# G07___PCB__2024-07-05.net
KiCad netlist of a schematic drawn in EasyEDA Pro
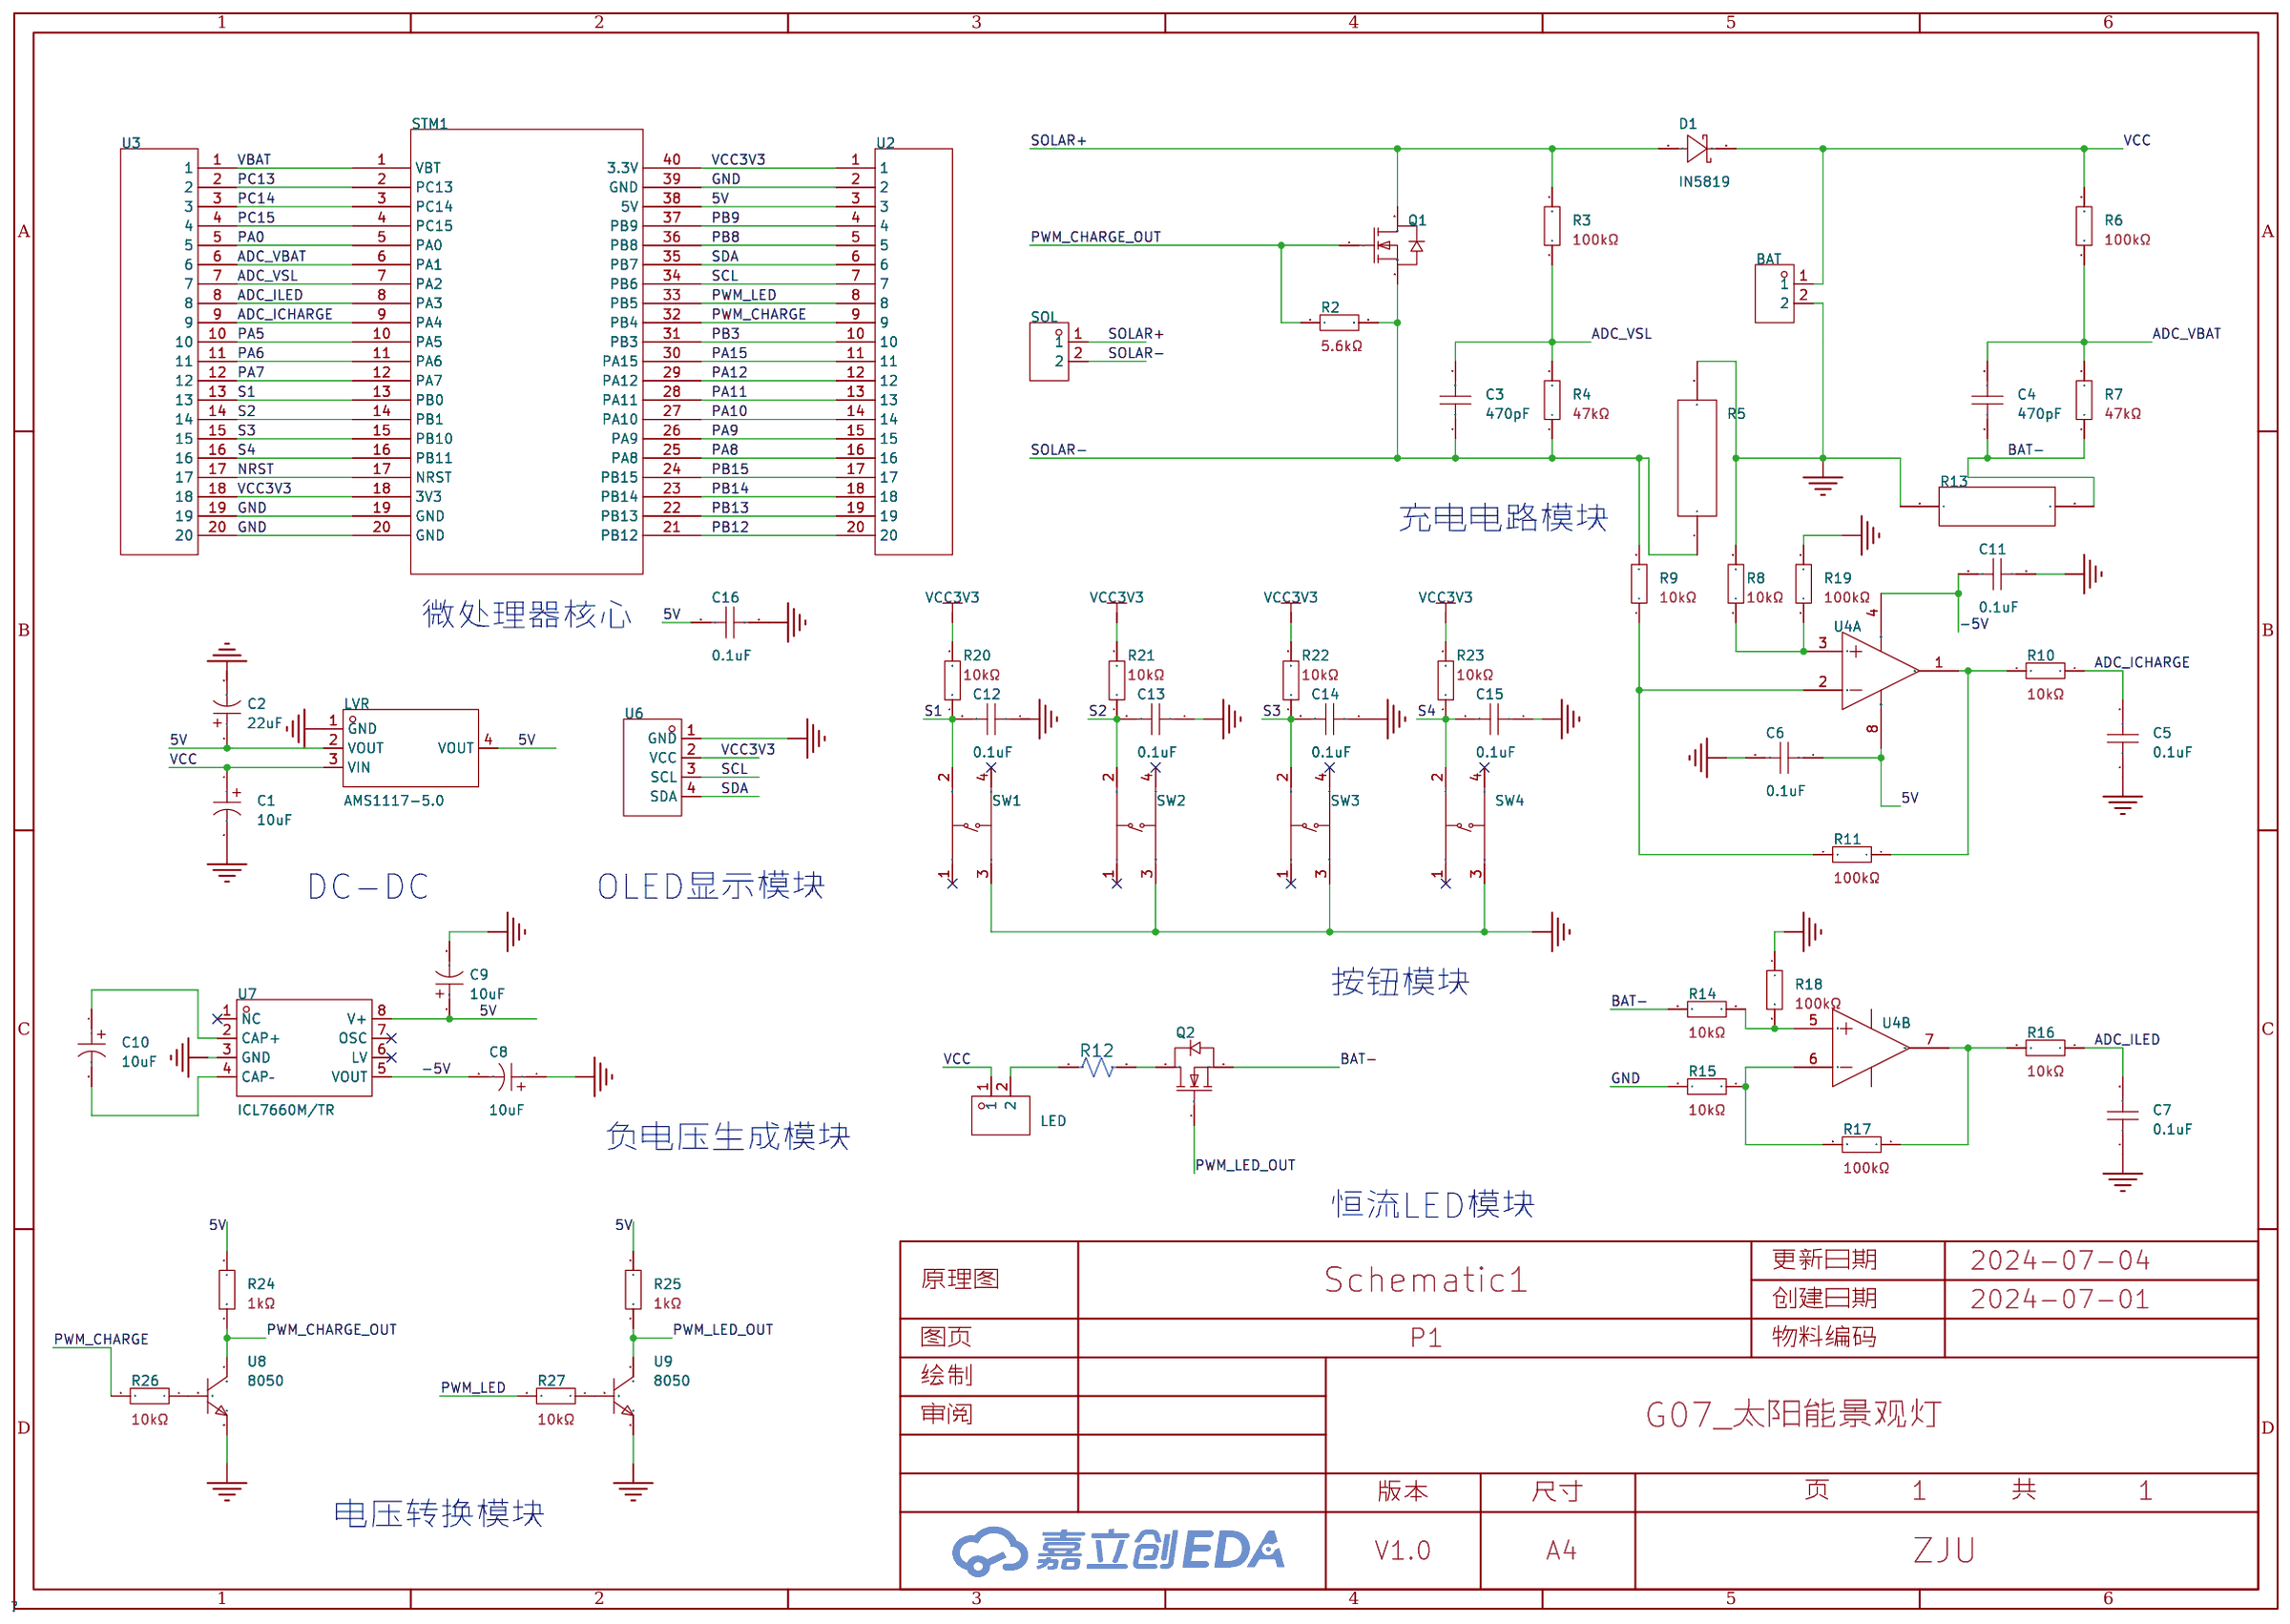
[diagram p0: schematic sheet]

(export (version "E")
  (design (tool "Eeschema 10.0.6"))
  (components
    (comp (ref "BAT")
      (value "KF2EDGK-5.08-2P")
      (footprint "easyedapro:CONN-TH_2P-P5.08_DB2EVC-5.08-2P-BK")
      (libsource (lib "easyedapro") (part "KF2EDGK-5.08-2P"))
    )
    (comp (ref "C1")
      (value "10uF")
      (footprint "easyedapro:C0511_直插电解")
      (description "C0511直插电解电容")
      (libsource (lib "easyedapro") (part "C0511"))
    )
    (comp (ref "C2")
      (value "22uF")
      (footprint "easyedapro:C0511_直插电解")
      (description "C0511直插电解电容")
      (libsource (lib "easyedapro") (part "C0511"))
    )
    (comp (ref "C3")
      (value "470pF")
      (footprint "easyedapro:CAP-TH_L5.3-W3.2-P2.54-D0.6-S2.65")
      (description "容值:100nF;精度:-20%~+80%;额定电压:50V;温度系数:Y5V;")
      (fields
        (field (name "Manufacturer Part") "CC1H104ZA1ED3F5O1100")
        (field (name "Manufacturer") "Dersonic(德尔创)")
      )
      (libsource (lib "easyedapro") (part "CC1H104ZA1ED3F5O1100"))
    )
    (comp (ref "C4")
      (value "470pF")
      (footprint "easyedapro:CAP-TH_L5.3-W3.2-P2.54-D0.6-S2.65")
      (description "容值:100nF;精度:-20%~+80%;额定电压:50V;温度系数:Y5V;")
      (fields
        (field (name "Manufacturer Part") "CC1H104ZA1ED3F5O1100")
        (field (name "Manufacturer") "Dersonic(德尔创)")
      )
      (libsource (lib "easyedapro") (part "CC1H104ZA1ED3F5O1100"))
    )
    (comp (ref "C5")
      (value "0.1uF")
      (footprint "easyedapro:CAP-TH_L5.3-W3.2-P2.54-D0.6-S2.65")
      (description "容值:100nF;精度:-20%~+80%;额定电压:50V;温度系数:Y5V;")
      (fields
        (field (name "Manufacturer Part") "CC1H104ZA1ED3F5O1100")
        (field (name "Manufacturer") "Dersonic(德尔创)")
      )
      (libsource (lib "easyedapro") (part "CC1H104ZA1ED3F5O1100"))
    )
    (comp (ref "C6")
      (value "0.1uF")
      (footprint "easyedapro:CAP-TH_L5.3-W3.2-P2.54-D0.6-S2.65")
      (description "容值:100nF;精度:-20%~+80%;额定电压:50V;温度系数:Y5V;")
      (fields
        (field (name "Manufacturer Part") "CC1H104ZA1ED3F5O1100")
        (field (name "Manufacturer") "Dersonic(德尔创)")
      )
      (libsource (lib "easyedapro") (part "CC1H104ZA1ED3F5O1100"))
    )
    (comp (ref "C7")
      (value "0.1uF")
      (footprint "easyedapro:CAP-TH_L5.3-W3.2-P2.54-D0.6-S2.65")
      (description "容值:100nF;精度:-20%~+80%;额定电压:50V;温度系数:Y5V;")
      (fields
        (field (name "Manufacturer Part") "CC1H104ZA1ED3F5O1100")
        (field (name "Manufacturer") "Dersonic(德尔创)")
      )
      (libsource (lib "easyedapro") (part "CC1H104ZA1ED3F5O1100"))
    )
    (comp (ref "C8")
      (value "10uF")
      (footprint "easyedapro:C0511_直插电解")
      (description "C0511直插电解电容")
      (libsource (lib "easyedapro") (part "C0511"))
    )
    (comp (ref "C9")
      (value "10uF")
      (footprint "easyedapro:C0511_直插电解")
      (description "C0511直插电解电容")
      (libsource (lib "easyedapro") (part "C0511"))
    )
    (comp (ref "C10")
      (value "10uF")
      (footprint "easyedapro:C0511_直插电解")
      (description "C0511直插电解电容")
      (libsource (lib "easyedapro") (part "C0511"))
    )
    (comp (ref "C11")
      (value "0.1uF")
      (footprint "easyedapro:CAP-TH_L5.3-W3.2-P2.54-D0.6-S2.65")
      (description "容值:100nF;精度:-20%~+80%;额定电压:50V;温度系数:Y5V;")
      (fields
        (field (name "Manufacturer Part") "CC1H104ZA1ED3F5O1100")
        (field (name "Manufacturer") "Dersonic(德尔创)")
      )
      (libsource (lib "easyedapro") (part "CC1H104ZA1ED3F5O1100"))
    )
    (comp (ref "C12")
      (value "0.1uF")
      (footprint "easyedapro:CAP-TH_L5.3-W3.2-P2.54-D0.6-S2.65")
      (description "容值:100nF;精度:-20%~+80%;额定电压:50V;温度系数:Y5V;")
      (fields
        (field (name "Manufacturer Part") "CC1H104ZA1ED3F5O1100")
        (field (name "Manufacturer") "Dersonic(德尔创)")
      )
      (libsource (lib "easyedapro") (part "CC1H104ZA1ED3F5O1100"))
    )
    (comp (ref "C13")
      (value "0.1uF")
      (footprint "easyedapro:CAP-TH_L5.3-W3.2-P2.54-D0.6-S2.65")
      (description "容值:100nF;精度:-20%~+80%;额定电压:50V;温度系数:Y5V;")
      (fields
        (field (name "Manufacturer Part") "CC1H104ZA1ED3F5O1100")
        (field (name "Manufacturer") "Dersonic(德尔创)")
      )
      (libsource (lib "easyedapro") (part "CC1H104ZA1ED3F5O1100"))
    )
    (comp (ref "C14")
      (value "0.1uF")
      (footprint "easyedapro:CAP-TH_L5.3-W3.2-P2.54-D0.6-S2.65")
      (description "容值:100nF;精度:-20%~+80%;额定电压:50V;温度系数:Y5V;")
      (fields
        (field (name "Manufacturer Part") "CC1H104ZA1ED3F5O1100")
        (field (name "Manufacturer") "Dersonic(德尔创)")
      )
      (libsource (lib "easyedapro") (part "CC1H104ZA1ED3F5O1100"))
    )
    (comp (ref "C15")
      (value "0.1uF")
      (footprint "easyedapro:CAP-TH_L5.3-W3.2-P2.54-D0.6-S2.65")
      (description "容值:100nF;精度:-20%~+80%;额定电压:50V;温度系数:Y5V;")
      (fields
        (field (name "Manufacturer Part") "CC1H104ZA1ED3F5O1100")
        (field (name "Manufacturer") "Dersonic(德尔创)")
      )
      (libsource (lib "easyedapro") (part "CC1H104ZA1ED3F5O1100"))
    )
    (comp (ref "C16")
      (value "0.1uF")
      (footprint "easyedapro:CAP-TH_L5.3-W3.2-P2.54-D0.6-S2.65")
      (description "容值:100nF;精度:-20%~+80%;额定电压:50V;温度系数:Y5V;")
      (fields
        (field (name "Manufacturer Part") "CC1H104ZA1ED3F5O1100")
        (field (name "Manufacturer") "Dersonic(德尔创)")
      )
      (libsource (lib "easyedapro") (part "CC1H104ZA1ED3F5O1100"))
    )
    (comp (ref "D1")
      (value "IN5819")
      (footprint "easyedapro:DO-41_BD2.4-L4.7-P8.70-D0.8-FD")
      (libsource (lib "easyedapro") (part "IN5819"))
    )
    (comp (ref "LED")
      (value "KF2EDGK-5.08-2P")
      (footprint "easyedapro:CONN-TH_2P-P5.08_DB2EVC-5.08-2P-BK")
      (libsource (lib "easyedapro") (part "KF2EDGK-5.08-2P"))
    )
    (comp (ref "LVR")
      (value "AMS1117-5.0")
      (footprint "easyedapro:SOT-223_L6.5-W3.5-P2.30-LS7.0-BR")
      (description "输出类型:固定;最大输入电压:12V;输出电压:5V;最大输出电流:1A;电源纹波抑制比(PSRR):68dB@(120Hz);输出极性:正极;")
      (fields (field (name "Manufacturer") "AMS"))
      (libsource (lib "easyedapro") (part "AMS1117-5.0"))
    )
    (comp (ref "Q1")
      (value "STP75NF75")
      (footprint "easyedapro:TO-220-3_L10.0-W4.5-P2.54-L")
      (fields (field (name "Manufacturer") "ST(意法半导体)"))
      (libsource (lib "easyedapro") (part "STP75NF75"))
    )
    (comp (ref "Q2")
      (value "STP75NF75")
      (footprint "easyedapro:TO-220-3_L10.0-W4.5-P2.54-L")
      (fields (field (name "Manufacturer") "ST(意法半导体)"))
      (libsource (lib "easyedapro") (part "STP75NF75"))
    )
    (comp (ref "R2")
      (value "AXIAL-0.4")
      (footprint "easyedapro:RES-TH_BD2.7-L8.8-P12.80-D0.5")
      (fields (field (name "Resistance") "5.6kΩ"))
      (libsource (lib "easyedapro") (part "AXIAL-0.4_C9900024059"))
    )
    (comp (ref "R3")
      (value "AXIAL-0.4")
      (footprint "easyedapro:RES-TH_BD2.7-L8.8-P12.80-D0.5")
      (fields (field (name "Resistance") "100kΩ"))
      (libsource (lib "easyedapro") (part "AXIAL-0.4_C9900024059"))
    )
    (comp (ref "R4")
      (value "AXIAL-0.4")
      (footprint "easyedapro:RES-TH_BD2.7-L8.8-P12.80-D0.5")
      (fields (field (name "Resistance") "47kΩ"))
      (libsource (lib "easyedapro") (part "AXIAL-0.4_C9900024059"))
    )
    (comp (ref "R5")
      (value "~")
      (footprint "easyedapro:采样电阻2*10mm")
      (libsource (lib "easyedapro") (part "采样电阻"))
    )
    (comp (ref "R6")
      (value "AXIAL-0.4")
      (footprint "easyedapro:RES-TH_BD2.7-L8.8-P12.80-D0.5")
      (fields (field (name "Resistance") "100kΩ"))
      (libsource (lib "easyedapro") (part "AXIAL-0.4_C9900024059"))
    )
    (comp (ref "R7")
      (value "AXIAL-0.4")
      (footprint "easyedapro:RES-TH_BD2.7-L8.8-P12.80-D0.5")
      (fields (field (name "Resistance") "47kΩ"))
      (libsource (lib "easyedapro") (part "AXIAL-0.4_C9900024059"))
    )
    (comp (ref "R8")
      (value "AXIAL-0.4")
      (footprint "easyedapro:RES-TH_BD2.7-L8.8-P12.80-D0.5")
      (fields (field (name "Resistance") "10kΩ"))
      (libsource (lib "easyedapro") (part "AXIAL-0.4_C9900024059"))
    )
    (comp (ref "R9")
      (value "AXIAL-0.4")
      (footprint "easyedapro:RES-TH_BD2.7-L8.8-P12.80-D0.5")
      (fields (field (name "Resistance") "10kΩ"))
      (libsource (lib "easyedapro") (part "AXIAL-0.4_C9900024059"))
    )
    (comp (ref "R10")
      (value "AXIAL-0.4")
      (footprint "easyedapro:RES-TH_BD2.7-L8.8-P12.80-D0.5")
      (fields (field (name "Resistance") "10kΩ"))
      (libsource (lib "easyedapro") (part "AXIAL-0.4_C9900024059"))
    )
    (comp (ref "R11")
      (value "AXIAL-0.4")
      (footprint "easyedapro:RES-TH_BD2.7-L8.8-P12.80-D0.5")
      (fields (field (name "Resistance") "100kΩ"))
      (libsource (lib "easyedapro") (part "AXIAL-0.4_C9900024059"))
    )
    (comp (ref "R12")
      (value "~")
      (footprint "easyedapro:AXIAL_0.6")
      (libsource (lib "easyedapro") (part "Resistor"))
    )
    (comp (ref "R13")
      (value "~")
      (footprint "easyedapro:采样电阻2*10mm")
      (libsource (lib "easyedapro") (part "采样电阻"))
    )
    (comp (ref "R14")
      (value "AXIAL-0.4")
      (footprint "easyedapro:RES-TH_BD2.7-L8.8-P12.80-D0.5")
      (fields (field (name "Resistance") "10kΩ"))
      (libsource (lib "easyedapro") (part "AXIAL-0.4_C9900024059"))
    )
    (comp (ref "R15")
      (value "AXIAL-0.4")
      (footprint "easyedapro:RES-TH_BD2.7-L8.8-P12.80-D0.5")
      (fields (field (name "Resistance") "10kΩ"))
      (libsource (lib "easyedapro") (part "AXIAL-0.4_C9900024059"))
    )
    (comp (ref "R16")
      (value "AXIAL-0.4")
      (footprint "easyedapro:RES-TH_BD2.7-L8.8-P12.80-D0.5")
      (fields (field (name "Resistance") "10kΩ"))
      (libsource (lib "easyedapro") (part "AXIAL-0.4_C9900024059"))
    )
    (comp (ref "R17")
      (value "AXIAL-0.4")
      (footprint "easyedapro:RES-TH_BD2.7-L8.8-P12.80-D0.5")
      (fields (field (name "Resistance") "100kΩ"))
      (libsource (lib "easyedapro") (part "AXIAL-0.4_C9900024059"))
    )
    (comp (ref "R18")
      (value "AXIAL-0.4")
      (footprint "easyedapro:RES-TH_BD2.7-L8.8-P12.80-D0.5")
      (fields (field (name "Resistance") "100kΩ"))
      (libsource (lib "easyedapro") (part "AXIAL-0.4_C9900024059"))
    )
    (comp (ref "R19")
      (value "AXIAL-0.4")
      (footprint "easyedapro:RES-TH_BD2.7-L8.8-P12.80-D0.5")
      (fields (field (name "Resistance") "100kΩ"))
      (libsource (lib "easyedapro") (part "AXIAL-0.4_C9900024059"))
    )
    (comp (ref "R20")
      (value "AXIAL-0.4")
      (footprint "easyedapro:RES-TH_BD2.7-L8.8-P12.80-D0.5")
      (fields (field (name "Resistance") "10kΩ"))
      (libsource (lib "easyedapro") (part "AXIAL-0.4_C9900024059"))
    )
    (comp (ref "R21")
      (value "AXIAL-0.4")
      (footprint "easyedapro:RES-TH_BD2.7-L8.8-P12.80-D0.5")
      (fields (field (name "Resistance") "10kΩ"))
      (libsource (lib "easyedapro") (part "AXIAL-0.4_C9900024059"))
    )
    (comp (ref "R22")
      (value "AXIAL-0.4")
      (footprint "easyedapro:RES-TH_BD2.7-L8.8-P12.80-D0.5")
      (fields (field (name "Resistance") "10kΩ"))
      (libsource (lib "easyedapro") (part "AXIAL-0.4_C9900024059"))
    )
    (comp (ref "R23")
      (value "AXIAL-0.4")
      (footprint "easyedapro:RES-TH_BD2.7-L8.8-P12.80-D0.5")
      (fields (field (name "Resistance") "10kΩ"))
      (libsource (lib "easyedapro") (part "AXIAL-0.4_C9900024059"))
    )
    (comp (ref "R24")
      (value "AXIAL-0.4")
      (footprint "easyedapro:RES-TH_BD2.7-L8.8-P12.80-D0.5")
      (fields (field (name "Resistance") "1kΩ"))
      (libsource (lib "easyedapro") (part "AXIAL-0.4_C9900024059"))
    )
    (comp (ref "R25")
      (value "AXIAL-0.4")
      (footprint "easyedapro:RES-TH_BD2.7-L8.8-P12.80-D0.5")
      (fields (field (name "Resistance") "1kΩ"))
      (libsource (lib "easyedapro") (part "AXIAL-0.4_C9900024059"))
    )
    (comp (ref "R26")
      (value "AXIAL-0.4")
      (footprint "easyedapro:RES-TH_BD2.7-L8.8-P12.80-D0.5")
      (fields (field (name "Resistance") "10kΩ"))
      (libsource (lib "easyedapro") (part "AXIAL-0.4_C9900024059"))
    )
    (comp (ref "R27")
      (value "AXIAL-0.4")
      (footprint "easyedapro:RES-TH_BD2.7-L8.8-P12.80-D0.5")
      (fields (field (name "Resistance") "10kΩ"))
      (libsource (lib "easyedapro") (part "AXIAL-0.4_C9900024059"))
    )
    (comp (ref "SOL")
      (value "KF2EDGK-5.08-2P")
      (footprint "easyedapro:CONN-TH_2P-P5.08_DB2EVC-5.08-2P-BK")
      (libsource (lib "easyedapro") (part "KF2EDGK-5.08-2P"))
    )
    (comp (ref "STM1")
      (value "STM32103C8T6")
      (footprint "easyedapro:STM32_C8T6_核心板")
      (libsource (lib "easyedapro") (part "STM32103C8T6_核心板"))
    )
    (comp (ref "SW1")
      (value "TS665CJ")
      (footprint "easyedapro:SW-TH_4P-L6.0-W6.0-P4.50-LS6.5")
      (description "电路结构:单刀单掷;按钮形状:圆形按钮;安装方式:直插;开关长度:6mm;开关宽度:6mm;开关高度:5mm;触点电流:50mA;额定电压(DC):12V;带灯:-;机械寿命:-;")
      (fields (field (name "Manufacturer") "SHOU HAN(首韩)"))
      (libsource (lib "easyedapro") (part "TS665CJ"))
    )
    (comp (ref "SW2")
      (value "TS665CJ")
      (footprint "easyedapro:SW-TH_4P-L6.0-W6.0-P4.50-LS6.5")
      (description "电路结构:单刀单掷;按钮形状:圆形按钮;安装方式:直插;开关长度:6mm;开关宽度:6mm;开关高度:5mm;触点电流:50mA;额定电压(DC):12V;带灯:-;机械寿命:-;")
      (fields (field (name "Manufacturer") "SHOU HAN(首韩)"))
      (libsource (lib "easyedapro") (part "TS665CJ"))
    )
    (comp (ref "SW3")
      (value "TS665CJ")
      (footprint "easyedapro:SW-TH_4P-L6.0-W6.0-P4.50-LS6.5")
      (description "电路结构:单刀单掷;按钮形状:圆形按钮;安装方式:直插;开关长度:6mm;开关宽度:6mm;开关高度:5mm;触点电流:50mA;额定电压(DC):12V;带灯:-;机械寿命:-;")
      (fields (field (name "Manufacturer") "SHOU HAN(首韩)"))
      (libsource (lib "easyedapro") (part "TS665CJ"))
    )
    (comp (ref "SW4")
      (value "TS665CJ")
      (footprint "easyedapro:SW-TH_4P-L6.0-W6.0-P4.50-LS6.5")
      (description "电路结构:单刀单掷;按钮形状:圆形按钮;安装方式:直插;开关长度:6mm;开关宽度:6mm;开关高度:5mm;触点电流:50mA;额定电压(DC):12V;带灯:-;机械寿命:-;")
      (fields (field (name "Manufacturer") "SHOU HAN(首韩)"))
      (libsource (lib "easyedapro") (part "TS665CJ"))
    )
    (comp (ref "U2")
      (value "~")
      (footprint "easyedapro:XH2.54_20P")
      (libsource (lib "easyedapro") (part "XH2.54_20P"))
    )
    (comp (ref "U3")
      (value "~")
      (footprint "easyedapro:XH2.54_20P")
      (libsource (lib "easyedapro") (part "XH2.54_20P"))
    )
    (comp (ref "U4")
      (value "LM358S")
      (footprint "easyedapro:SOP-8_L4.9-W3.9-P1.27-LS6.0-BL")
      (description "放大器数:-;增益带宽积(GBP):1MHz;压摆率(SR):0.3V/us;")
      (fields (field (name "Manufacturer") "Slkor(萨科微)"))
      (libsource (lib "easyedapro") (part "LM358S_C408270"))
    )
    (comp (ref "U6")
      (value "HS96L03W2C03")
      (footprint "easyedapro:OLED-TH_L27.8-W27.2-P2.54_C9900033791")
      (description "主控芯片:SSD1315;接口类型:I2C;尺寸(inch):0.96;像素分辨率:128x64;")
      (fields (field (name "Manufacturer") "HS(汉昇)"))
      (libsource (lib "easyedapro") (part "HS96L03W2C03"))
    )
    (comp (ref "U7")
      (value "ICL7660M/TR")
      (footprint "easyedapro:SOP-8_L4.9-W3.9-P1.27-LS6.0-BL")
      (fields (field (name "Manufacturer") "HGSEMI(华冠)"))
      (libsource (lib "easyedapro") (part "ICL7660M/TR"))
    )
    (comp (ref "U8")
      (value "8050")
      (footprint "easyedapro:TO-92-3_L4.8-W3.7-P2.54-R")
      (fields (field (name "Manufacturer") "BLUE ROCKET(蓝箭)"))
      (libsource (lib "easyedapro") (part "8050"))
    )
    (comp (ref "U9")
      (value "8050")
      (footprint "easyedapro:TO-92-3_L4.8-W3.7-P2.54-R")
      (fields (field (name "Manufacturer") "BLUE ROCKET(蓝箭)"))
      (libsource (lib "easyedapro") (part "8050"))
    )
  )
  (nets
    (net (code "1") (name "/-5V") (class "Default")
      (node (ref "C11") (pin "2") (pinfunction "2_2") (pintype "unspecified"))
      (node (ref "C8") (pin "2") (pinfunction "2_2") (pintype "input"))
      (node (ref "U4") (pin "4") (pinfunction "GND_4") (pintype "unspecified"))
      (node (ref "U7") (pin "5") (pinfunction "VOUT_5") (pintype "unspecified"))
    )
    (net (code "2") (name "/5V") (class "Default")
      (node (ref "C16") (pin "2") (pinfunction "2_2") (pintype "unspecified"))
      (node (ref "C2") (pin "1") (pinfunction "1_1") (pintype "input"))
      (node (ref "C6") (pin "1") (pinfunction "1_1") (pintype "unspecified"))
      (node (ref "C9") (pin "1") (pinfunction "1_1") (pintype "input"))
      (node (ref "LVR") (pin "2") (pinfunction "VOUT_2") (pintype "unspecified"))
      (node (ref "LVR") (pin "4") (pinfunction "VOUT_4") (pintype "unspecified"))
      (node (ref "R24") (pin "2") (pinfunction "2_2") (pintype "unspecified"))
      (node (ref "R25") (pin "2") (pinfunction "2_2") (pintype "unspecified"))
      (node (ref "STM1") (pin "38") (pinfunction "5V_38") (pintype "unspecified"))
      (node (ref "U2") (pin "3") (pinfunction "3_3") (pintype "input"))
      (node (ref "U4") (pin "8") (pinfunction "VCC_8") (pintype "unspecified"))
      (node (ref "U7") (pin "8") (pinfunction "V+_8") (pintype "unspecified"))
    )
    (net (code "3") (name "/ADC_ICHARGE") (class "Default")
      (node (ref "C5") (pin "2") (pinfunction "2_2") (pintype "unspecified"))
      (node (ref "R10") (pin "1") (pinfunction "1_1") (pintype "unspecified"))
      (node (ref "STM1") (pin "9") (pinfunction "PA4_9") (pintype "unspecified"))
      (node (ref "U3") (pin "9") (pinfunction "9_9") (pintype "input"))
    )
    (net (code "4") (name "/ADC_ILED") (class "Default")
      (node (ref "C7") (pin "2") (pinfunction "2_2") (pintype "unspecified"))
      (node (ref "R16") (pin "1") (pinfunction "1_1") (pintype "unspecified"))
      (node (ref "STM1") (pin "8") (pinfunction "PA3_8") (pintype "unspecified"))
      (node (ref "U3") (pin "8") (pinfunction "8_8") (pintype "input"))
    )
    (net (code "5") (name "/ADC_VBAT") (class "Default")
      (node (ref "C4") (pin "2") (pinfunction "2_2") (pintype "unspecified"))
      (node (ref "R6") (pin "1") (pinfunction "1_1") (pintype "unspecified"))
      (node (ref "R7") (pin "2") (pinfunction "2_2") (pintype "unspecified"))
      (node (ref "STM1") (pin "6") (pinfunction "PA1_6") (pintype "unspecified"))
      (node (ref "U3") (pin "6") (pinfunction "6_6") (pintype "input"))
    )
    (net (code "6") (name "/ADC_VSL") (class "Default")
      (node (ref "C3") (pin "2") (pinfunction "2_2") (pintype "unspecified"))
      (node (ref "R3") (pin "1") (pinfunction "1_1") (pintype "unspecified"))
      (node (ref "R4") (pin "2") (pinfunction "2_2") (pintype "unspecified"))
      (node (ref "STM1") (pin "7") (pinfunction "PA2_7") (pintype "unspecified"))
      (node (ref "U3") (pin "7") (pinfunction "7_7") (pintype "input"))
    )
    (net (code "7") (name "/BAT-") (class "Default")
      (node (ref "C4") (pin "1") (pinfunction "1_1") (pintype "unspecified"))
      (node (ref "Q2") (pin "3") (pinfunction "S_3") (pintype "input"))
      (node (ref "R13") (pin "2") (pinfunction "2_2") (pintype "input"))
      (node (ref "R14") (pin "2") (pinfunction "2_2") (pintype "unspecified"))
      (node (ref "R7") (pin "1") (pinfunction "1_1") (pintype "unspecified"))
    )
    (net (code "8") (name "/NRST") (class "Default")
      (node (ref "STM1") (pin "17") (pinfunction "NRST_17") (pintype "unspecified"))
      (node (ref "U3") (pin "17") (pinfunction "17_17") (pintype "input"))
    )
    (net (code "9") (name "/PA0") (class "Default")
      (node (ref "STM1") (pin "5") (pinfunction "PA0_5") (pintype "unspecified"))
      (node (ref "U3") (pin "5") (pinfunction "5_5") (pintype "input"))
    )
    (net (code "10") (name "/PA5") (class "Default")
      (node (ref "STM1") (pin "10") (pinfunction "PA5_10") (pintype "unspecified"))
      (node (ref "U3") (pin "10") (pinfunction "10_10") (pintype "input"))
    )
    (net (code "11") (name "/PA6") (class "Default")
      (node (ref "STM1") (pin "11") (pinfunction "PA6_11") (pintype "unspecified"))
      (node (ref "U3") (pin "11") (pinfunction "11_11") (pintype "input"))
    )
    (net (code "12") (name "/PA7") (class "Default")
      (node (ref "STM1") (pin "12") (pinfunction "PA7_12") (pintype "unspecified"))
      (node (ref "U3") (pin "12") (pinfunction "12_12") (pintype "input"))
    )
    (net (code "13") (name "/PA8") (class "Default")
      (node (ref "STM1") (pin "25") (pinfunction "PA8_25") (pintype "unspecified"))
      (node (ref "U2") (pin "16") (pinfunction "16_16") (pintype "input"))
    )
    (net (code "14") (name "/PA9") (class "Default")
      (node (ref "STM1") (pin "26") (pinfunction "PA9_26") (pintype "unspecified"))
      (node (ref "U2") (pin "15") (pinfunction "15_15") (pintype "input"))
    )
    (net (code "15") (name "/PA10") (class "Default")
      (node (ref "STM1") (pin "27") (pinfunction "PA10_27") (pintype "unspecified"))
      (node (ref "U2") (pin "14") (pinfunction "14_14") (pintype "input"))
    )
    (net (code "16") (name "/PA11") (class "Default")
      (node (ref "STM1") (pin "28") (pinfunction "PA11_28") (pintype "unspecified"))
      (node (ref "U2") (pin "13") (pinfunction "13_13") (pintype "input"))
    )
    (net (code "17") (name "/PA12") (class "Default")
      (node (ref "STM1") (pin "29") (pinfunction "PA12_29") (pintype "unspecified"))
      (node (ref "U2") (pin "12") (pinfunction "12_12") (pintype "input"))
    )
    (net (code "18") (name "/PA15") (class "Default")
      (node (ref "STM1") (pin "30") (pinfunction "PA15_30") (pintype "unspecified"))
      (node (ref "U2") (pin "11") (pinfunction "11_11") (pintype "input"))
    )
    (net (code "19") (name "/PB3") (class "Default")
      (node (ref "STM1") (pin "31") (pinfunction "PB3_31") (pintype "unspecified"))
      (node (ref "U2") (pin "10") (pinfunction "10_10") (pintype "input"))
    )
    (net (code "20") (name "/PB8") (class "Default")
      (node (ref "STM1") (pin "36") (pinfunction "PB8_36") (pintype "unspecified"))
      (node (ref "U2") (pin "5") (pinfunction "5_5") (pintype "input"))
    )
    (net (code "21") (name "/PB9") (class "Default")
      (node (ref "STM1") (pin "37") (pinfunction "PB9_37") (pintype "unspecified"))
      (node (ref "U2") (pin "4") (pinfunction "4_4") (pintype "input"))
    )
    (net (code "22") (name "/PB12") (class "Default")
      (node (ref "STM1") (pin "21") (pinfunction "PB12_21") (pintype "unspecified"))
      (node (ref "U2") (pin "20") (pinfunction "20_20") (pintype "input"))
    )
    (net (code "23") (name "/PB13") (class "Default")
      (node (ref "STM1") (pin "22") (pinfunction "PB13_22") (pintype "unspecified"))
      (node (ref "U2") (pin "19") (pinfunction "19_19") (pintype "input"))
    )
    (net (code "24") (name "/PB14") (class "Default")
      (node (ref "STM1") (pin "23") (pinfunction "PB14_23") (pintype "unspecified"))
      (node (ref "U2") (pin "18") (pinfunction "18_18") (pintype "input"))
    )
    (net (code "25") (name "/PB15") (class "Default")
      (node (ref "STM1") (pin "24") (pinfunction "PB15_24") (pintype "unspecified"))
      (node (ref "U2") (pin "17") (pinfunction "17_17") (pintype "input"))
    )
    (net (code "26") (name "/PC13") (class "Default")
      (node (ref "STM1") (pin "2") (pinfunction "PC13_2") (pintype "unspecified"))
      (node (ref "U3") (pin "2") (pinfunction "2_2") (pintype "input"))
    )
    (net (code "27") (name "/PC14") (class "Default")
      (node (ref "STM1") (pin "3") (pinfunction "PC14_3") (pintype "unspecified"))
      (node (ref "U3") (pin "3") (pinfunction "3_3") (pintype "input"))
    )
    (net (code "28") (name "/PC15") (class "Default")
      (node (ref "STM1") (pin "4") (pinfunction "PC15_4") (pintype "unspecified"))
      (node (ref "U3") (pin "4") (pinfunction "4_4") (pintype "input"))
    )
    (net (code "29") (name "/PWM_CHARGE") (class "Default")
      (node (ref "R26") (pin "2") (pinfunction "2_2") (pintype "unspecified"))
      (node (ref "STM1") (pin "32") (pinfunction "PB4_32") (pintype "unspecified"))
      (node (ref "U2") (pin "9") (pinfunction "9_9") (pintype "input"))
    )
    (net (code "30") (name "/PWM_CHARGE_OUT") (class "Default")
      (node (ref "Q1") (pin "1") (pinfunction "G_1") (pintype "input"))
      (node (ref "R2") (pin "1") (pinfunction "1_1") (pintype "unspecified"))
      (node (ref "R24") (pin "1") (pinfunction "1_1") (pintype "unspecified"))
      (node (ref "U8") (pin "1") (pinfunction "C_1") (pintype "input"))
    )
    (net (code "31") (name "/PWM_LED") (class "Default")
      (node (ref "R27") (pin "2") (pinfunction "2_2") (pintype "unspecified"))
      (node (ref "STM1") (pin "33") (pinfunction "PB5_33") (pintype "unspecified"))
      (node (ref "U2") (pin "8") (pinfunction "8_8") (pintype "input"))
    )
    (net (code "32") (name "/PWM_LED_OUT") (class "Default")
      (node (ref "Q2") (pin "1") (pinfunction "G_1") (pintype "input"))
      (node (ref "R25") (pin "1") (pinfunction "1_1") (pintype "unspecified"))
      (node (ref "U9") (pin "1") (pinfunction "C_1") (pintype "input"))
    )
    (net (code "33") (name "/S1") (class "Default")
      (node (ref "C12") (pin "2") (pinfunction "2_2") (pintype "unspecified"))
      (node (ref "R20") (pin "1") (pinfunction "1_1") (pintype "unspecified"))
      (node (ref "STM1") (pin "13") (pinfunction "PB0_13") (pintype "unspecified"))
      (node (ref "SW1") (pin "2") (pinfunction "B_2") (pintype "unspecified"))
      (node (ref "U3") (pin "13") (pinfunction "13_13") (pintype "input"))
    )
    (net (code "34") (name "/S2") (class "Default")
      (node (ref "C13") (pin "2") (pinfunction "2_2") (pintype "unspecified"))
      (node (ref "R21") (pin "1") (pinfunction "1_1") (pintype "unspecified"))
      (node (ref "STM1") (pin "14") (pinfunction "PB1_14") (pintype "unspecified"))
      (node (ref "SW2") (pin "2") (pinfunction "B_2") (pintype "unspecified"))
      (node (ref "U3") (pin "14") (pinfunction "14_14") (pintype "input"))
    )
    (net (code "35") (name "/S3") (class "Default")
      (node (ref "C14") (pin "2") (pinfunction "2_2") (pintype "unspecified"))
      (node (ref "R22") (pin "1") (pinfunction "1_1") (pintype "unspecified"))
      (node (ref "STM1") (pin "15") (pinfunction "PB10_15") (pintype "unspecified"))
      (node (ref "SW3") (pin "2") (pinfunction "B_2") (pintype "unspecified"))
      (node (ref "U3") (pin "15") (pinfunction "15_15") (pintype "input"))
    )
    (net (code "36") (name "/S4") (class "Default")
      (node (ref "C15") (pin "2") (pinfunction "2_2") (pintype "unspecified"))
      (node (ref "R23") (pin "1") (pinfunction "1_1") (pintype "unspecified"))
      (node (ref "STM1") (pin "16") (pinfunction "PB11_16") (pintype "unspecified"))
      (node (ref "SW4") (pin "2") (pinfunction "B_2") (pintype "unspecified"))
      (node (ref "U3") (pin "16") (pinfunction "16_16") (pintype "input"))
    )
    (net (code "37") (name "/SCL") (class "Default")
      (node (ref "STM1") (pin "34") (pinfunction "PB6_34") (pintype "unspecified"))
      (node (ref "U2") (pin "7") (pinfunction "7_7") (pintype "input"))
      (node (ref "U6") (pin "3") (pinfunction "SCL_3") (pintype "unspecified"))
    )
    (net (code "38") (name "/SDA") (class "Default")
      (node (ref "STM1") (pin "35") (pinfunction "PB7_35") (pintype "unspecified"))
      (node (ref "U2") (pin "6") (pinfunction "6_6") (pintype "input"))
      (node (ref "U6") (pin "4") (pinfunction "SDA_4") (pintype "unspecified"))
    )
    (net (code "39") (name "/SOLAR+") (class "Default")
      (node (ref "D1") (pin "1") (pinfunction "A_1") (pintype "unspecified"))
      (node (ref "Q1") (pin "2") (pinfunction "D_2") (pintype "input"))
      (node (ref "R3") (pin "2") (pinfunction "2_2") (pintype "unspecified"))
      (node (ref "SOL") (pin "1") (pinfunction "1_1") (pintype "unspecified"))
    )
    (net (code "40") (name "/SOLAR-") (class "Default")
      (node (ref "C3") (pin "1") (pinfunction "1_1") (pintype "unspecified"))
      (node (ref "Q1") (pin "3") (pinfunction "S_3") (pintype "input"))
      (node (ref "R2") (pin "2") (pinfunction "2_2") (pintype "unspecified"))
      (node (ref "R4") (pin "1") (pinfunction "1_1") (pintype "unspecified"))
      (node (ref "R5") (pin "1") (pinfunction "1_1") (pintype "input"))
      (node (ref "R9") (pin "2") (pinfunction "2_2") (pintype "unspecified"))
      (node (ref "SOL") (pin "2") (pinfunction "2_2") (pintype "unspecified"))
    )
    (net (code "41") (name "/VBAT") (class "Default")
      (node (ref "STM1") (pin "1") (pinfunction "VBT_1") (pintype "unspecified"))
      (node (ref "U3") (pin "1") (pinfunction "1_1") (pintype "input"))
    )
    (net (code "42") (name "/VCC") (class "Default")
      (node (ref "BAT") (pin "1") (pinfunction "1_1") (pintype "unspecified"))
      (node (ref "C1") (pin "1") (pinfunction "1_1") (pintype "input"))
      (node (ref "D1") (pin "2") (pinfunction "K_2") (pintype "unspecified"))
      (node (ref "LED") (pin "1") (pinfunction "1_1") (pintype "unspecified"))
      (node (ref "LVR") (pin "3") (pinfunction "VIN_3") (pintype "unspecified"))
      (node (ref "R6") (pin "2") (pinfunction "2_2") (pintype "unspecified"))
    )
    (net (code "43") (name "GND") (class "Default")
      (node (ref "BAT") (pin "2") (pinfunction "2_2") (pintype "unspecified"))
      (node (ref "C1") (pin "2") (pinfunction "2_2") (pintype "input"))
      (node (ref "C11") (pin "1") (pinfunction "1_1") (pintype "unspecified"))
      (node (ref "C12") (pin "1") (pinfunction "1_1") (pintype "unspecified"))
      (node (ref "C13") (pin "1") (pinfunction "1_1") (pintype "unspecified"))
      (node (ref "C14") (pin "1") (pinfunction "1_1") (pintype "unspecified"))
      (node (ref "C15") (pin "1") (pinfunction "1_1") (pintype "unspecified"))
      (node (ref "C16") (pin "1") (pinfunction "1_1") (pintype "unspecified"))
      (node (ref "C2") (pin "2") (pinfunction "2_2") (pintype "input"))
      (node (ref "C5") (pin "1") (pinfunction "1_1") (pintype "unspecified"))
      (node (ref "C6") (pin "2") (pinfunction "2_2") (pintype "unspecified"))
      (node (ref "C7") (pin "1") (pinfunction "1_1") (pintype "unspecified"))
      (node (ref "C8") (pin "1") (pinfunction "1_1") (pintype "input"))
      (node (ref "C9") (pin "2") (pinfunction "2_2") (pintype "input"))
      (node (ref "LVR") (pin "1") (pinfunction "GND_1") (pintype "unspecified"))
      (node (ref "R13") (pin "1") (pinfunction "1_1") (pintype "input"))
      (node (ref "R15") (pin "2") (pinfunction "2_2") (pintype "unspecified"))
      (node (ref "R18") (pin "1") (pinfunction "1_1") (pintype "unspecified"))
      (node (ref "R19") (pin "2") (pinfunction "2_2") (pintype "unspecified"))
      (node (ref "R5") (pin "2") (pinfunction "2_2") (pintype "input"))
      (node (ref "R8") (pin "2") (pinfunction "2_2") (pintype "unspecified"))
      (node (ref "STM1") (pin "19") (pinfunction "GND_19") (pintype "unspecified"))
      (node (ref "STM1") (pin "20") (pinfunction "GND_20") (pintype "unspecified"))
      (node (ref "STM1") (pin "39") (pinfunction "GND_39") (pintype "unspecified"))
      (node (ref "SW1") (pin "3") (pinfunction "C_3") (pintype "unspecified"))
      (node (ref "SW2") (pin "3") (pinfunction "C_3") (pintype "unspecified"))
      (node (ref "SW3") (pin "3") (pinfunction "C_3") (pintype "unspecified"))
      (node (ref "SW4") (pin "3") (pinfunction "C_3") (pintype "unspecified"))
      (node (ref "U2") (pin "2") (pinfunction "2_2") (pintype "input"))
      (node (ref "U3") (pin "19") (pinfunction "19_19") (pintype "input"))
      (node (ref "U3") (pin "20") (pinfunction "20_20") (pintype "input"))
      (node (ref "U6") (pin "1") (pinfunction "GND_1") (pintype "unspecified"))
      (node (ref "U7") (pin "3") (pinfunction "GND_3") (pintype "unspecified"))
      (node (ref "U8") (pin "3") (pinfunction "E_3") (pintype "input"))
      (node (ref "U9") (pin "3") (pinfunction "E_3") (pintype "input"))
    )
    (net (code "44") (name "Net-(LED-Pad2)") (class "Default")
      (node (ref "LED") (pin "2") (pinfunction "2_2") (pintype "unspecified"))
      (node (ref "R12") (pin "1") (pinfunction "1_1") (pintype "unspecified"))
    )
    (net (code "45") (name "Net-(Q2-D)") (class "Default")
      (node (ref "Q2") (pin "2") (pinfunction "D_2") (pintype "input"))
      (node (ref "R12") (pin "2") (pinfunction "2_2") (pintype "unspecified"))
    )
    (net (code "46") (name "Net-(U4A-IN1+)") (class "Default")
      (node (ref "R19") (pin "1") (pinfunction "1_1") (pintype "unspecified"))
      (node (ref "R8") (pin "1") (pinfunction "1_1") (pintype "unspecified"))
      (node (ref "U4") (pin "3") (pinfunction "IN1+_3") (pintype "unspecified"))
    )
    (net (code "47") (name "Net-(U4A-IN1-)") (class "Default")
      (node (ref "R11") (pin "2") (pinfunction "2_2") (pintype "unspecified"))
      (node (ref "R9") (pin "1") (pinfunction "1_1") (pintype "unspecified"))
      (node (ref "U4") (pin "2") (pinfunction "IN1-_2") (pintype "unspecified"))
    )
    (net (code "48") (name "Net-(U4A-OUT1)") (class "Default")
      (node (ref "R10") (pin "2") (pinfunction "2_2") (pintype "unspecified"))
      (node (ref "R11") (pin "1") (pinfunction "1_1") (pintype "unspecified"))
      (node (ref "U4") (pin "1") (pinfunction "OUT1_1") (pintype "output"))
    )
    (net (code "49") (name "Net-(U4B-IN2+)") (class "Default")
      (node (ref "R14") (pin "1") (pinfunction "1_1") (pintype "unspecified"))
      (node (ref "R18") (pin "2") (pinfunction "2_2") (pintype "unspecified"))
      (node (ref "U4") (pin "5") (pinfunction "IN2+_5") (pintype "unspecified"))
    )
    (net (code "50") (name "Net-(U4B-IN2-)") (class "Default")
      (node (ref "R15") (pin "1") (pinfunction "1_1") (pintype "unspecified"))
      (node (ref "R17") (pin "2") (pinfunction "2_2") (pintype "unspecified"))
      (node (ref "U4") (pin "6") (pinfunction "IN2-_6") (pintype "unspecified"))
    )
    (net (code "51") (name "Net-(U4B-OUT2)") (class "Default")
      (node (ref "R16") (pin "2") (pinfunction "2_2") (pintype "unspecified"))
      (node (ref "R17") (pin "1") (pinfunction "1_1") (pintype "unspecified"))
      (node (ref "U4") (pin "7") (pinfunction "OUT2_7") (pintype "output"))
    )
    (net (code "52") (name "Net-(U7-CAP+)") (class "Default")
      (node (ref "C10") (pin "1") (pinfunction "1_1") (pintype "input"))
      (node (ref "U7") (pin "2") (pinfunction "CAP+_2") (pintype "unspecified"))
    )
    (net (code "53") (name "Net-(U7-CAP–)") (class "Default")
      (node (ref "C10") (pin "2") (pinfunction "2_2") (pintype "input"))
      (node (ref "U7") (pin "4") (pinfunction "CAP–_4") (pintype "unspecified"))
    )
    (net (code "54") (name "Net-(U8-B)") (class "Default")
      (node (ref "R26") (pin "1") (pinfunction "1_1") (pintype "unspecified"))
      (node (ref "U8") (pin "2") (pinfunction "B_2") (pintype "input"))
    )
    (net (code "55") (name "Net-(U9-B)") (class "Default")
      (node (ref "R27") (pin "1") (pinfunction "1_1") (pintype "unspecified"))
      (node (ref "U9") (pin "2") (pinfunction "B_2") (pintype "input"))
    )
    (net (code "56") (name "VCC3V3") (class "Default")
      (node (ref "R20") (pin "2") (pinfunction "2_2") (pintype "unspecified"))
      (node (ref "R21") (pin "2") (pinfunction "2_2") (pintype "unspecified"))
      (node (ref "R22") (pin "2") (pinfunction "2_2") (pintype "unspecified"))
      (node (ref "R23") (pin "2") (pinfunction "2_2") (pintype "unspecified"))
      (node (ref "STM1") (pin "18") (pinfunction "3V3_18") (pintype "unspecified"))
      (node (ref "STM1") (pin "40") (pinfunction "3.3V_40") (pintype "unspecified"))
      (node (ref "U2") (pin "1") (pinfunction "1_1") (pintype "input"))
      (node (ref "U3") (pin "18") (pinfunction "18_18") (pintype "input"))
      (node (ref "U6") (pin "2") (pinfunction "VCC_2") (pintype "unspecified"))
    )
    (net (code "57") (name "unconnected-(SW1-A-Pad1)") (class "Default")
      (node (ref "SW1") (pin "1") (pinfunction "A_1") (pintype "unspecified+no_connect"))
    )
    (net (code "58") (name "unconnected-(SW1-D-Pad4)") (class "Default")
      (node (ref "SW1") (pin "4") (pinfunction "D_4") (pintype "unspecified+no_connect"))
    )
    (net (code "59") (name "unconnected-(SW2-A-Pad1)") (class "Default")
      (node (ref "SW2") (pin "1") (pinfunction "A_1") (pintype "unspecified+no_connect"))
    )
    (net (code "60") (name "unconnected-(SW2-D-Pad4)") (class "Default")
      (node (ref "SW2") (pin "4") (pinfunction "D_4") (pintype "unspecified+no_connect"))
    )
    (net (code "61") (name "unconnected-(SW3-A-Pad1)") (class "Default")
      (node (ref "SW3") (pin "1") (pinfunction "A_1") (pintype "unspecified+no_connect"))
    )
    (net (code "62") (name "unconnected-(SW3-D-Pad4)") (class "Default")
      (node (ref "SW3") (pin "4") (pinfunction "D_4") (pintype "unspecified+no_connect"))
    )
    (net (code "63") (name "unconnected-(SW4-A-Pad1)") (class "Default")
      (node (ref "SW4") (pin "1") (pinfunction "A_1") (pintype "unspecified+no_connect"))
    )
    (net (code "64") (name "unconnected-(SW4-D-Pad4)") (class "Default")
      (node (ref "SW4") (pin "4") (pinfunction "D_4") (pintype "unspecified+no_connect"))
    )
    (net (code "65") (name "unconnected-(U7-LV-Pad6)") (class "Default")
      (node (ref "U7") (pin "6") (pinfunction "LV_6") (pintype "unspecified+no_connect"))
    )
    (net (code "66") (name "unconnected-(U7-NC-Pad1)") (class "Default")
      (node (ref "U7") (pin "1") (pinfunction "NC_1") (pintype "unspecified+no_connect"))
    )
    (net (code "67") (name "unconnected-(U7-OSC-Pad7)") (class "Default")
      (node (ref "U7") (pin "7") (pinfunction "OSC_7") (pintype "unspecified+no_connect"))
    )
  )
)
